# tritiled22_cr2354_oslon_reverse.net
KiCad netlist of a schematic drawn in EAGLE
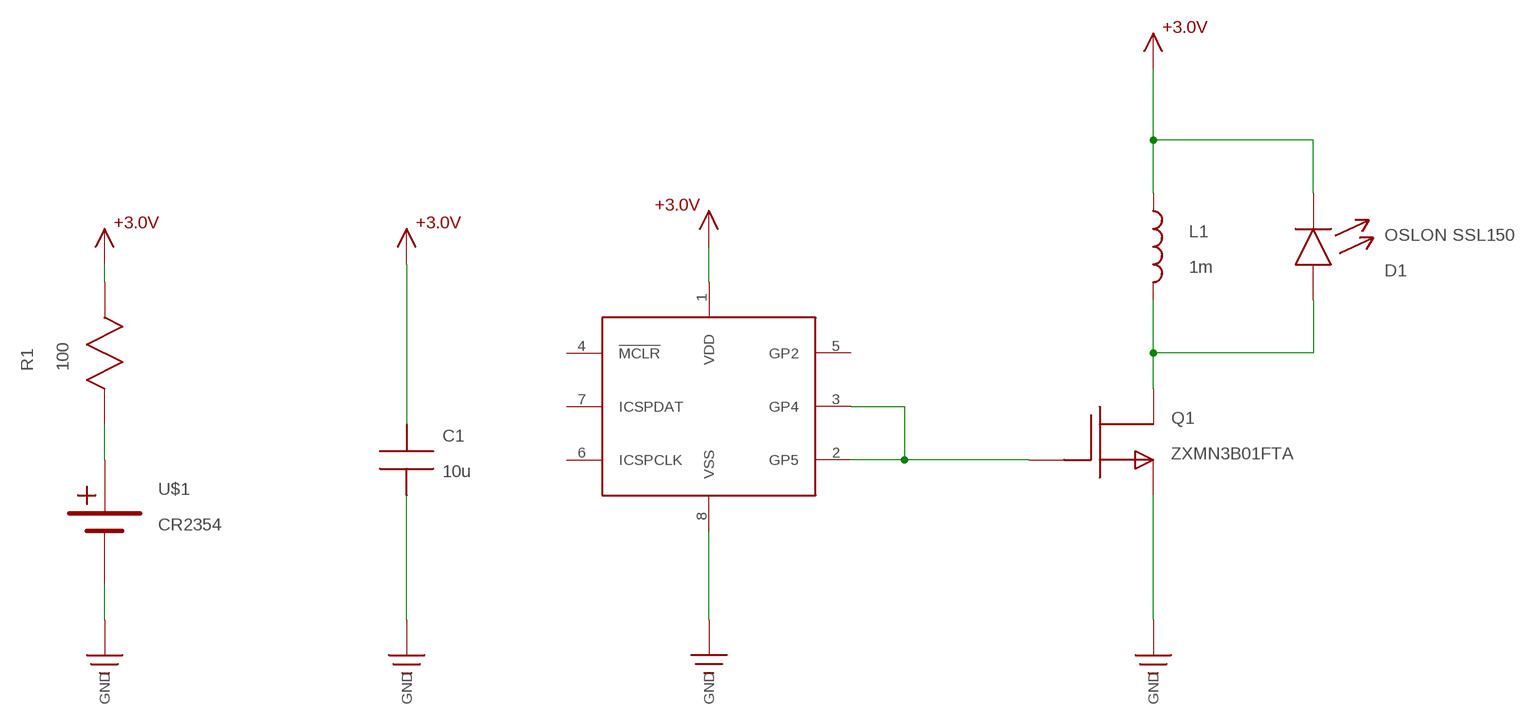
[diagram p0: schematic, sheet 1]

(export (version "E")
  (design (tool "Eeschema 10.0.6"))
  (components
    (comp (ref "C1")
      (value "10u")
      (footprint "eagle-import:1206")
      (libsource (lib "eagle-import") (part "C1206"))
    )
    (comp (ref "D1")
      (value "OSLON SSL150")
      (footprint "eagle-import:OSLON_3030_LED")
      (libsource (lib "eagle-import") (part "LEDSSL150"))
    )
    (comp (ref "L1")
      (value "1m")
      (footprint "eagle-import:SRR6028_INDUCTOR")
      (libsource (lib "eagle-import") (part "SRR6028_INDUCTOR"))
    )
    (comp (ref "Q1")
      (value "ZXMN3B01FTA")
      (footprint "eagle-import:SOT-23")
      (libsource (lib "eagle-import") (part "ZXMN3B01FSOT23"))
    )
    (comp (ref "R1")
      (value "100")
      (footprint "eagle-import:R1206")
      (libsource (lib "eagle-import") (part "R1206"))
    )
    (comp (ref "U$1")
      (value "CR2354")
      (footprint "eagle-import:CR2354_TABBED")
      (libsource (lib "eagle-import") (part "CR2354_TABBED"))
    )
    (comp (ref "U1")
      (value "PIC12LF1571")
      (footprint "eagle-import:SOIC8")
      (libsource (lib "eagle-import") (part "PIC12LF1571"))
    )
  )
  (nets
    (net (code "1") (name "+3.0V") (class "Default")
      (node (ref "C1") (pin "P$1") (pinfunction "P$1_P$1") (pintype "bidirectional"))
      (node (ref "D1") (pin "C") (pinfunction "C_C") (pintype "bidirectional"))
      (node (ref "L1") (pin "P$1") (pinfunction "1_P$1") (pintype "passive"))
      (node (ref "R1") (pin "P$2") (pinfunction "P$2_P$2") (pintype "bidirectional"))
      (node (ref "U1") (pin "1") (pinfunction "VDD_1") (pintype "bidirectional"))
    )
    (net (code "2") (name "GND") (class "Default")
      (node (ref "C1") (pin "P$2") (pinfunction "P$2_P$2") (pintype "bidirectional"))
      (node (ref "Q1") (pin "2") (pinfunction "S_2") (pintype "bidirectional"))
      (node (ref "U$1") (pin "GND") (pinfunction "0V_GND") (pintype "power_in"))
      (node (ref "U1") (pin "8") (pinfunction "VSS_8") (pintype "bidirectional"))
    )
    (net (code "3") (name "Net-(L1-2)") (class "Default")
      (node (ref "D1") (pin "A") (pinfunction "A_A") (pintype "bidirectional"))
      (node (ref "L1") (pin "P$2") (pinfunction "2_P$2") (pintype "passive"))
      (node (ref "Q1") (pin "3") (pinfunction "D_3") (pintype "bidirectional"))
    )
    (net (code "4") (name "Net-(Q1-G)") (class "Default")
      (node (ref "Q1") (pin "1") (pinfunction "G_1") (pintype "bidirectional"))
      (node (ref "U1") (pin "2") (pinfunction "GP5_2") (pintype "bidirectional"))
      (node (ref "U1") (pin "3") (pinfunction "GP4_3") (pintype "bidirectional"))
    )
    (net (code "5") (name "Net-(U$1-+V)") (class "Default")
      (node (ref "R1") (pin "P$1") (pinfunction "P$1_P$1") (pintype "bidirectional"))
      (node (ref "U$1") (pin "+3V") (pinfunction "+V_+3V") (pintype "power_in"))
    )
    (net (code "6") (name "unconnected-(U1-GP2-Pad5)") (class "Default")
      (node (ref "U1") (pin "5") (pinfunction "GP2_5") (pintype "bidirectional"))
    )
    (net (code "7") (name "unconnected-(U1-ICSPCLK-Pad6)") (class "Default")
      (node (ref "U1") (pin "6") (pinfunction "ICSPCLK_6") (pintype "bidirectional"))
    )
    (net (code "8") (name "unconnected-(U1-ICSPDAT-Pad7)") (class "Default")
      (node (ref "U1") (pin "7") (pinfunction "ICSPDAT_7") (pintype "bidirectional"))
    )
    (net (code "9") (name "unconnected-(U1-~{MCLR}-Pad4)") (class "Default")
      (node (ref "U1") (pin "4") (pinfunction "~{MCLR}_4") (pintype "bidirectional"))
    )
  )
)
